# MCU_breakout.net
KiCad netlist of a schematic drawn in EAGLE
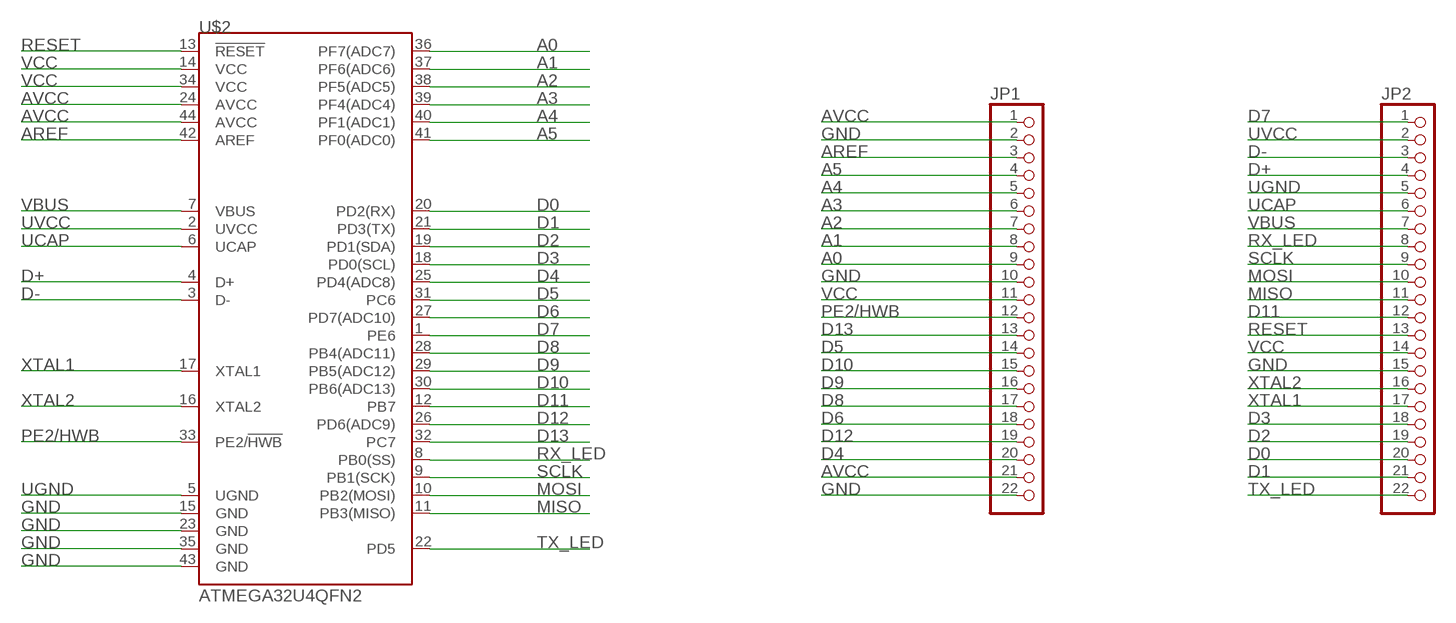
[diagram p0: schematic, sheet 1]

(export (version "E")
  (design (tool "Eeschema 10.0.6"))
  (components
    (comp (ref "JP1")
      (value "PINHD-1X22")
      (footprint "eagle-import:1X22")
      (libsource (lib "eagle-import") (part "PINHD-1X22"))
    )
    (comp (ref "JP2")
      (value "PINHD-1X22")
      (footprint "eagle-import:1X22")
      (libsource (lib "eagle-import") (part "PINHD-1X22"))
    )
    (comp (ref "U$2")
      (value "ATMEGA32U4QFN2")
      (footprint "eagle-import:QFN-44-NOPAD")
      (libsource (lib "eagle-import") (part "ATMEGA32U4QFN2"))
    )
  )
  (nets
    (net (code "1") (name "/A0") (class "Default")
      (node (ref "JP1") (pin "9") (pinfunction "9_9") (pintype "passive"))
      (node (ref "U$2") (pin "36") (pinfunction "PF7(ADC7)_36") (pintype "bidirectional"))
    )
    (net (code "2") (name "/A1") (class "Default")
      (node (ref "JP1") (pin "8") (pinfunction "8_8") (pintype "passive"))
      (node (ref "U$2") (pin "37") (pinfunction "PF6(ADC6)_37") (pintype "bidirectional"))
    )
    (net (code "3") (name "/A2") (class "Default")
      (node (ref "JP1") (pin "7") (pinfunction "7_7") (pintype "passive"))
      (node (ref "U$2") (pin "38") (pinfunction "PF5(ADC5)_38") (pintype "bidirectional"))
    )
    (net (code "4") (name "/A3") (class "Default")
      (node (ref "JP1") (pin "6") (pinfunction "6_6") (pintype "passive"))
      (node (ref "U$2") (pin "39") (pinfunction "PF4(ADC4)_39") (pintype "bidirectional"))
    )
    (net (code "5") (name "/A4") (class "Default")
      (node (ref "JP1") (pin "5") (pinfunction "5_5") (pintype "passive"))
      (node (ref "U$2") (pin "40") (pinfunction "PF1(ADC1)_40") (pintype "bidirectional"))
    )
    (net (code "6") (name "/A5") (class "Default")
      (node (ref "JP1") (pin "4") (pinfunction "4_4") (pintype "passive"))
      (node (ref "U$2") (pin "41") (pinfunction "PF0(ADC0)_41") (pintype "bidirectional"))
    )
    (net (code "7") (name "/AREF") (class "Default")
      (node (ref "JP1") (pin "3") (pinfunction "3_3") (pintype "passive"))
      (node (ref "U$2") (pin "42") (pinfunction "AREF_42") (pintype "bidirectional"))
    )
    (net (code "8") (name "/AVCC") (class "Default")
      (node (ref "JP1") (pin "1") (pinfunction "1_1") (pintype "passive"))
      (node (ref "JP1") (pin "21") (pinfunction "21_21") (pintype "passive"))
      (node (ref "U$2") (pin "24") (pinfunction "AVCC_24") (pintype "bidirectional"))
      (node (ref "U$2") (pin "44") (pinfunction "AVCC_44") (pintype "bidirectional"))
    )
    (net (code "9") (name "/D+") (class "Default")
      (node (ref "JP2") (pin "4") (pinfunction "4_4") (pintype "passive"))
      (node (ref "U$2") (pin "4") (pinfunction "D+_4") (pintype "bidirectional"))
    )
    (net (code "10") (name "/D-") (class "Default")
      (node (ref "JP2") (pin "3") (pinfunction "3_3") (pintype "passive"))
      (node (ref "U$2") (pin "3") (pinfunction "D-_3") (pintype "bidirectional"))
    )
    (net (code "11") (name "/D0") (class "Default")
      (node (ref "JP2") (pin "20") (pinfunction "20_20") (pintype "passive"))
      (node (ref "U$2") (pin "20") (pinfunction "PD2(RX)_20") (pintype "bidirectional"))
    )
    (net (code "12") (name "/D1") (class "Default")
      (node (ref "JP2") (pin "21") (pinfunction "21_21") (pintype "passive"))
      (node (ref "U$2") (pin "21") (pinfunction "PD3(TX)_21") (pintype "bidirectional"))
    )
    (net (code "13") (name "/D2") (class "Default")
      (node (ref "JP2") (pin "19") (pinfunction "19_19") (pintype "passive"))
      (node (ref "U$2") (pin "19") (pinfunction "PD1(SDA)_19") (pintype "bidirectional"))
    )
    (net (code "14") (name "/D3") (class "Default")
      (node (ref "JP2") (pin "18") (pinfunction "18_18") (pintype "passive"))
      (node (ref "U$2") (pin "18") (pinfunction "PD0(SCL)_18") (pintype "bidirectional"))
    )
    (net (code "15") (name "/D4") (class "Default")
      (node (ref "JP1") (pin "20") (pinfunction "20_20") (pintype "passive"))
      (node (ref "U$2") (pin "25") (pinfunction "PD4(ADC8)_25") (pintype "bidirectional"))
    )
    (net (code "16") (name "/D5") (class "Default")
      (node (ref "JP1") (pin "14") (pinfunction "14_14") (pintype "passive"))
      (node (ref "U$2") (pin "31") (pinfunction "PC6_31") (pintype "bidirectional"))
    )
    (net (code "17") (name "/D6") (class "Default")
      (node (ref "JP1") (pin "18") (pinfunction "18_18") (pintype "passive"))
      (node (ref "U$2") (pin "27") (pinfunction "PD7(ADC10)_27") (pintype "bidirectional"))
    )
    (net (code "18") (name "/D7") (class "Default")
      (node (ref "JP2") (pin "1") (pinfunction "1_1") (pintype "passive"))
      (node (ref "U$2") (pin "1") (pinfunction "PE6_1") (pintype "bidirectional"))
    )
    (net (code "19") (name "/D8") (class "Default")
      (node (ref "JP1") (pin "17") (pinfunction "17_17") (pintype "passive"))
      (node (ref "U$2") (pin "28") (pinfunction "PB4(ADC11)_28") (pintype "bidirectional"))
    )
    (net (code "20") (name "/D9") (class "Default")
      (node (ref "JP1") (pin "16") (pinfunction "16_16") (pintype "passive"))
      (node (ref "U$2") (pin "29") (pinfunction "PB5(ADC12)_29") (pintype "bidirectional"))
    )
    (net (code "21") (name "/D10") (class "Default")
      (node (ref "JP1") (pin "15") (pinfunction "15_15") (pintype "passive"))
      (node (ref "U$2") (pin "30") (pinfunction "PB6(ADC13)_30") (pintype "bidirectional"))
    )
    (net (code "22") (name "/D11") (class "Default")
      (node (ref "JP2") (pin "12") (pinfunction "12_12") (pintype "passive"))
      (node (ref "U$2") (pin "12") (pinfunction "PB7_12") (pintype "bidirectional"))
    )
    (net (code "23") (name "/D12") (class "Default")
      (node (ref "JP1") (pin "19") (pinfunction "19_19") (pintype "passive"))
      (node (ref "U$2") (pin "26") (pinfunction "PD6(ADC9)_26") (pintype "bidirectional"))
    )
    (net (code "24") (name "/D13") (class "Default")
      (node (ref "JP1") (pin "13") (pinfunction "13_13") (pintype "passive"))
      (node (ref "U$2") (pin "32") (pinfunction "PC7_32") (pintype "bidirectional"))
    )
    (net (code "25") (name "/GND") (class "Default")
      (node (ref "JP1") (pin "10") (pinfunction "10_10") (pintype "passive"))
      (node (ref "JP1") (pin "2") (pinfunction "2_2") (pintype "passive"))
      (node (ref "JP1") (pin "22") (pinfunction "22_22") (pintype "passive"))
      (node (ref "JP2") (pin "15") (pinfunction "15_15") (pintype "passive"))
      (node (ref "U$2") (pin "15") (pinfunction "GND_15") (pintype "bidirectional"))
      (node (ref "U$2") (pin "23") (pinfunction "GND_23") (pintype "bidirectional"))
      (node (ref "U$2") (pin "35") (pinfunction "GND_35") (pintype "bidirectional"))
      (node (ref "U$2") (pin "43") (pinfunction "GND_43") (pintype "bidirectional"))
    )
    (net (code "26") (name "/MISO") (class "Default")
      (node (ref "JP2") (pin "11") (pinfunction "11_11") (pintype "passive"))
      (node (ref "U$2") (pin "11") (pinfunction "PB3(MISO)_11") (pintype "bidirectional"))
    )
    (net (code "27") (name "/MOSI") (class "Default")
      (node (ref "JP2") (pin "10") (pinfunction "10_10") (pintype "passive"))
      (node (ref "U$2") (pin "10") (pinfunction "PB2(MOSI)_10") (pintype "bidirectional"))
    )
    (net (code "28") (name "/PE2{slash}HWB") (class "Default")
      (node (ref "JP1") (pin "12") (pinfunction "12_12") (pintype "passive"))
      (node (ref "U$2") (pin "33") (pinfunction "PE2/~{HWB}_33") (pintype "bidirectional"))
    )
    (net (code "29") (name "/RESET") (class "Default")
      (node (ref "JP2") (pin "13") (pinfunction "13_13") (pintype "passive"))
      (node (ref "U$2") (pin "13") (pinfunction "~{RESET}_13") (pintype "bidirectional"))
    )
    (net (code "30") (name "/RX_LED") (class "Default")
      (node (ref "JP2") (pin "8") (pinfunction "8_8") (pintype "passive"))
      (node (ref "U$2") (pin "8") (pinfunction "PB0(SS)_8") (pintype "bidirectional"))
    )
    (net (code "31") (name "/SCLK") (class "Default")
      (node (ref "JP2") (pin "9") (pinfunction "9_9") (pintype "passive"))
      (node (ref "U$2") (pin "9") (pinfunction "PB1(SCK)_9") (pintype "bidirectional"))
    )
    (net (code "32") (name "/TX_LED") (class "Default")
      (node (ref "JP2") (pin "22") (pinfunction "22_22") (pintype "passive"))
      (node (ref "U$2") (pin "22") (pinfunction "PD5_22") (pintype "bidirectional"))
    )
    (net (code "33") (name "/UCAP") (class "Default")
      (node (ref "JP2") (pin "6") (pinfunction "6_6") (pintype "passive"))
      (node (ref "U$2") (pin "6") (pinfunction "UCAP_6") (pintype "bidirectional"))
    )
    (net (code "34") (name "/UGND") (class "Default")
      (node (ref "JP2") (pin "5") (pinfunction "5_5") (pintype "passive"))
      (node (ref "U$2") (pin "5") (pinfunction "UGND_5") (pintype "bidirectional"))
    )
    (net (code "35") (name "/UVCC") (class "Default")
      (node (ref "JP2") (pin "2") (pinfunction "2_2") (pintype "passive"))
      (node (ref "U$2") (pin "2") (pinfunction "UVCC_2") (pintype "bidirectional"))
    )
    (net (code "36") (name "/VBUS") (class "Default")
      (node (ref "JP2") (pin "7") (pinfunction "7_7") (pintype "passive"))
      (node (ref "U$2") (pin "7") (pinfunction "VBUS_7") (pintype "bidirectional"))
    )
    (net (code "37") (name "/VCC") (class "Default")
      (node (ref "JP1") (pin "11") (pinfunction "11_11") (pintype "passive"))
      (node (ref "JP2") (pin "14") (pinfunction "14_14") (pintype "passive"))
      (node (ref "U$2") (pin "14") (pinfunction "VCC_14") (pintype "bidirectional"))
      (node (ref "U$2") (pin "34") (pinfunction "VCC_34") (pintype "bidirectional"))
    )
    (net (code "38") (name "/XTAL1") (class "Default")
      (node (ref "JP2") (pin "17") (pinfunction "17_17") (pintype "passive"))
      (node (ref "U$2") (pin "17") (pinfunction "XTAL1_17") (pintype "bidirectional"))
    )
    (net (code "39") (name "/XTAL2") (class "Default")
      (node (ref "JP2") (pin "16") (pinfunction "16_16") (pintype "passive"))
      (node (ref "U$2") (pin "16") (pinfunction "XTAL2_16") (pintype "bidirectional"))
    )
  )
)
